# MicroFans.net
KiCad netlist of a schematic drawn in EAGLE
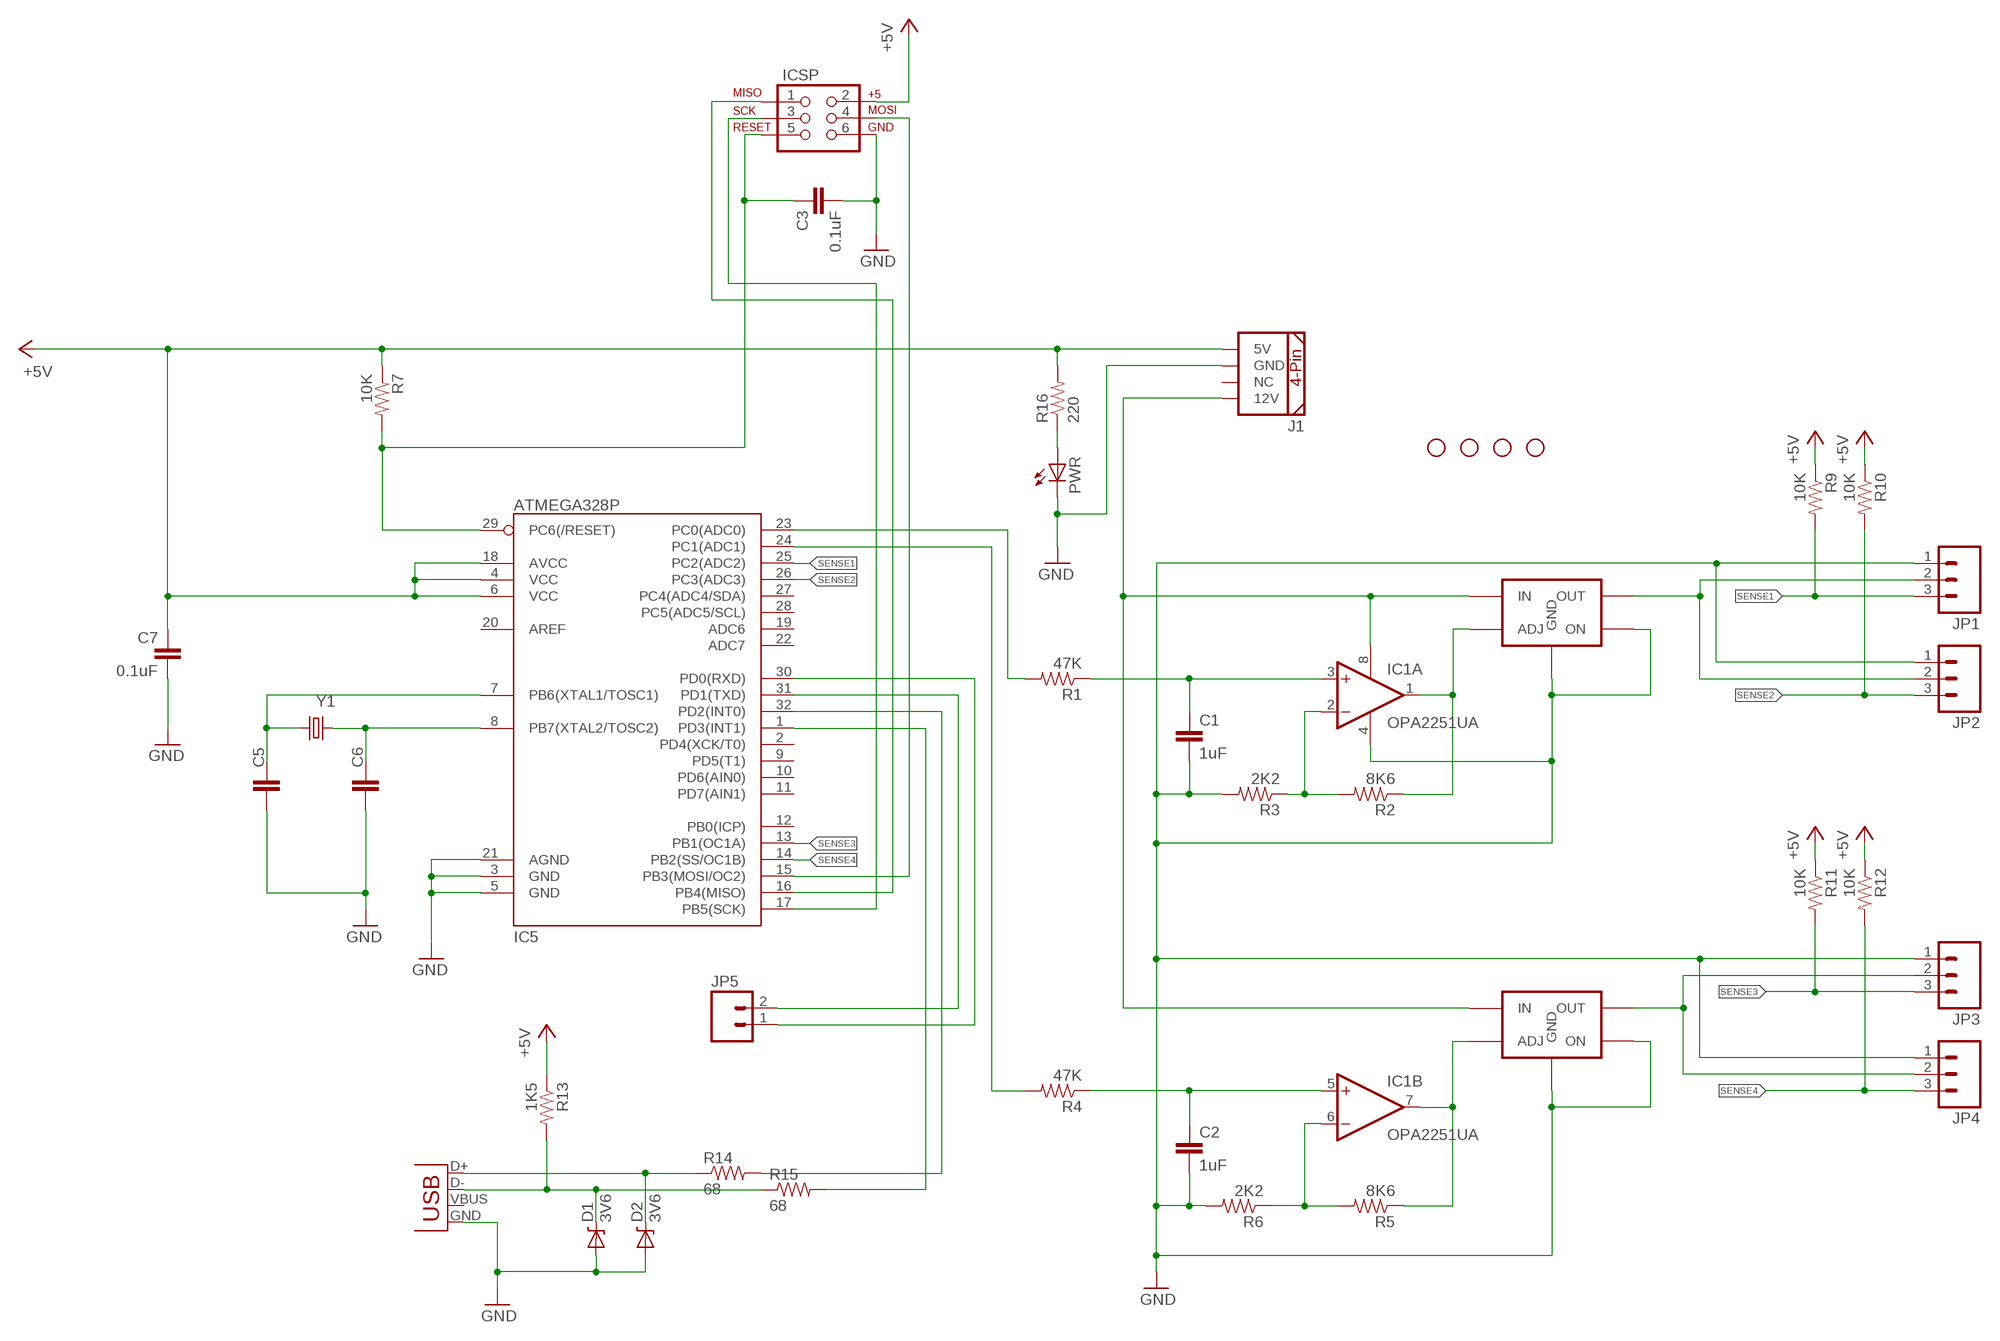
[diagram p0: schematic, sheet 1]

(export (version "E")
  (design (tool "Eeschema 10.0.6"))
  (components
    (comp (ref "C1")
      (value "1uF")
      (footprint "eagle-import:0805")
      (libsource (lib "eagle-import") (part "CAP0805"))
    )
    (comp (ref "C2")
      (value "1uF")
      (footprint "eagle-import:0805")
      (libsource (lib "eagle-import") (part "CAP0805"))
    )
    (comp (ref "C3")
      (value "0.1uF")
      (footprint "eagle-import:0805")
      (libsource (lib "eagle-import") (part "CAP0805"))
    )
    (comp (ref "C5")
      (value ".22uF")
      (footprint "eagle-import:0805")
      (libsource (lib "eagle-import") (part "CAP0805"))
    )
    (comp (ref "C6")
      (value ".22uF")
      (footprint "eagle-import:0805")
      (libsource (lib "eagle-import") (part "CAP0805"))
    )
    (comp (ref "C7")
      (value "0.1uF")
      (footprint "eagle-import:0805")
      (libsource (lib "eagle-import") (part "CAP0805"))
    )
    (comp (ref "D1")
      (value "3V6")
      (footprint "eagle-import:SOD-323")
      (libsource (lib "eagle-import") (part "DIODE-ZENER-BZT52"))
    )
    (comp (ref "D2")
      (value "3V6")
      (footprint "eagle-import:SOD-323")
      (libsource (lib "eagle-import") (part "DIODE-ZENER-BZT52"))
    )
    (comp (ref "HOLE1")
      (value "STAND-OFF")
      (footprint "eagle-import:STAND-OFF")
      (libsource (lib "eagle-import") (part "STAND-OFF"))
    )
    (comp (ref "HOLE2")
      (value "STAND-OFF")
      (footprint "eagle-import:STAND-OFF")
      (libsource (lib "eagle-import") (part "STAND-OFF"))
    )
    (comp (ref "HOLE3")
      (value "STAND-OFF")
      (footprint "eagle-import:STAND-OFF")
      (libsource (lib "eagle-import") (part "STAND-OFF"))
    )
    (comp (ref "HOLE4")
      (value "STAND-OFF")
      (footprint "eagle-import:STAND-OFF")
      (libsource (lib "eagle-import") (part "STAND-OFF"))
    )
    (comp (ref "IC1")
      (value "OPA2251UA")
      (footprint "eagle-import:SO08")
      (libsource (lib "eagle-import") (part "OPA2UA251"))
    )
    (comp (ref "IC3")
      (value "LM2941TO220-V")
      (footprint "eagle-import:TO220-51")
      (libsource (lib "eagle-import") (part "LM2941TO220-V"))
    )
    (comp (ref "IC4")
      (value "LM2941TO220-V")
      (footprint "eagle-import:TO220-51")
      (libsource (lib "eagle-import") (part "LM2941TO220-V"))
    )
    (comp (ref "IC5")
      (value "ATMEGA328P")
      (footprint "eagle-import:TQFP32-08")
      (libsource (lib "eagle-import") (part "ATMEGA328_SMT"))
    )
    (comp (ref "ICSP")
      (value "AVR_SPI_PRG_6PTH")
      (footprint "eagle-import:2X3")
      (libsource (lib "eagle-import") (part "AVR_SPI_PRG_6PTH"))
    )
    (comp (ref "J1")
      (value "COMPUTER-PERIPHERAL-POWERVERTICAL")
      (footprint "eagle-import:COMPUTER-PERIPHERAL-POWER")
      (libsource (lib "eagle-import") (part "COMPUTER-PERIPHERAL-POWERVERTICAL"))
    )
    (comp (ref "JP1")
      (value "M03POLAR")
      (footprint "eagle-import:MOLEX-1X3")
      (libsource (lib "eagle-import") (part "M03POLAR"))
    )
    (comp (ref "JP2")
      (value "M03POLAR")
      (footprint "eagle-import:MOLEX-1X3")
      (libsource (lib "eagle-import") (part "M03POLAR"))
    )
    (comp (ref "JP3")
      (value "M03POLAR")
      (footprint "eagle-import:MOLEX-1X3")
      (libsource (lib "eagle-import") (part "M03POLAR"))
    )
    (comp (ref "JP4")
      (value "M03POLAR")
      (footprint "eagle-import:MOLEX-1X3")
      (libsource (lib "eagle-import") (part "M03POLAR"))
    )
    (comp (ref "JP5")
      (value "M02PTH")
      (footprint "eagle-import:1X02")
      (libsource (lib "eagle-import") (part "M02PTH"))
    )
    (comp (ref "PWR")
      (value "LED1206")
      (footprint "eagle-import:LED-1206")
      (libsource (lib "eagle-import") (part "LED1206"))
    )
    (comp (ref "R1")
      (value "47K")
      (footprint "eagle-import:0805")
      (libsource (lib "eagle-import") (part "RESISTOR0805-RES"))
    )
    (comp (ref "R2")
      (value "8K6")
      (footprint "eagle-import:0805")
      (libsource (lib "eagle-import") (part "RESISTOR0805-RES"))
    )
    (comp (ref "R3")
      (value "2K2")
      (footprint "eagle-import:0805")
      (libsource (lib "eagle-import") (part "RESISTOR0805-RES"))
    )
    (comp (ref "R4")
      (value "47K")
      (footprint "eagle-import:0805")
      (libsource (lib "eagle-import") (part "RESISTOR0805-RES"))
    )
    (comp (ref "R5")
      (value "8K6")
      (footprint "eagle-import:0805")
      (libsource (lib "eagle-import") (part "RESISTOR0805-RES"))
    )
    (comp (ref "R6")
      (value "2K2")
      (footprint "eagle-import:0805")
      (libsource (lib "eagle-import") (part "RESISTOR0805-RES"))
    )
    (comp (ref "R7")
      (value "10K")
      (footprint "eagle-import:0805")
      (libsource (lib "eagle-import") (part "RESISTOR0805-RES"))
    )
    (comp (ref "R9")
      (value "10K")
      (footprint "eagle-import:0805")
      (libsource (lib "eagle-import") (part "RESISTOR0805-RES"))
    )
    (comp (ref "R10")
      (value "10K")
      (footprint "eagle-import:0805")
      (libsource (lib "eagle-import") (part "RESISTOR0805-RES"))
    )
    (comp (ref "R11")
      (value "10K")
      (footprint "eagle-import:0805")
      (libsource (lib "eagle-import") (part "RESISTOR0805-RES"))
    )
    (comp (ref "R12")
      (value "10K")
      (footprint "eagle-import:0805")
      (libsource (lib "eagle-import") (part "RESISTOR0805-RES"))
    )
    (comp (ref "R13")
      (value "1K5")
      (footprint "eagle-import:0805")
      (libsource (lib "eagle-import") (part "RESISTOR0805-RES"))
    )
    (comp (ref "R14")
      (value "68")
      (footprint "eagle-import:0805")
      (libsource (lib "eagle-import") (part "RESISTOR0805-RES"))
    )
    (comp (ref "R15")
      (value "68")
      (footprint "eagle-import:0805")
      (libsource (lib "eagle-import") (part "RESISTOR0805-RES"))
    )
    (comp (ref "R16")
      (value "220")
      (footprint "eagle-import:0805")
      (libsource (lib "eagle-import") (part "RESISTOR0805-RES"))
    )
    (comp (ref "USB")
      (value "USB-A-SMD")
      (footprint "eagle-import:USB-A-S-NOSILK-FEMALE")
      (libsource (lib "eagle-import") (part "USB-A-SMD"))
    )
    (comp (ref "Y1")
      (value "16MHZ")
      (footprint "eagle-import:HC49US")
      (libsource (lib "eagle-import") (part "CRYSTALHC49US"))
    )
  )
  (nets
    (net (code "1") (name "+5V") (class "Default")
      (node (ref "C7") (pin "1") (pinfunction "1_1") (pintype "passive"))
      (node (ref "IC5") (pin "18") (pinfunction "AVCC_18") (pintype "bidirectional"))
      (node (ref "IC5") (pin "4") (pinfunction "VCC_4") (pintype "bidirectional"))
      (node (ref "IC5") (pin "6") (pinfunction "VCC_6") (pintype "bidirectional"))
      (node (ref "ICSP") (pin "2") (pinfunction "2_2") (pintype "passive"))
      (node (ref "J1") (pin "5V") (pinfunction "5V_5V") (pintype "passive"))
      (node (ref "R10") (pin "1") (pinfunction "1_1") (pintype "passive"))
      (node (ref "R11") (pin "1") (pinfunction "1_1") (pintype "passive"))
      (node (ref "R12") (pin "1") (pinfunction "1_1") (pintype "passive"))
      (node (ref "R13") (pin "1") (pinfunction "1_1") (pintype "passive"))
      (node (ref "R16") (pin "2") (pinfunction "2_2") (pintype "passive"))
      (node (ref "R7") (pin "1") (pinfunction "1_1") (pintype "passive"))
      (node (ref "R9") (pin "1") (pinfunction "1_1") (pintype "passive"))
    )
    (net (code "2") (name "GND") (class "Default")
      (node (ref "C1") (pin "2") (pinfunction "2_2") (pintype "passive"))
      (node (ref "C2") (pin "2") (pinfunction "2_2") (pintype "passive"))
      (node (ref "C3") (pin "2") (pinfunction "2_2") (pintype "passive"))
      (node (ref "C5") (pin "2") (pinfunction "2_2") (pintype "passive"))
      (node (ref "C6") (pin "2") (pinfunction "2_2") (pintype "passive"))
      (node (ref "C7") (pin "2") (pinfunction "2_2") (pintype "passive"))
      (node (ref "D1") (pin "2") (pinfunction "A_2") (pintype "passive"))
      (node (ref "D2") (pin "2") (pinfunction "A_2") (pintype "passive"))
      (node (ref "IC1") (pin "4") (pinfunction "V-_4") (pintype "power_in"))
      (node (ref "IC3") (pin "2") (pinfunction "ON_2") (pintype "bidirectional"))
      (node (ref "IC3") (pin "3") (pinfunction "GND_3") (pintype "bidirectional"))
      (node (ref "IC4") (pin "2") (pinfunction "ON_2") (pintype "bidirectional"))
      (node (ref "IC4") (pin "3") (pinfunction "GND_3") (pintype "bidirectional"))
      (node (ref "IC5") (pin "21") (pinfunction "AGND_21") (pintype "bidirectional"))
      (node (ref "IC5") (pin "3") (pinfunction "GND_3") (pintype "bidirectional"))
      (node (ref "IC5") (pin "5") (pinfunction "GND_5") (pintype "bidirectional"))
      (node (ref "ICSP") (pin "6") (pinfunction "6_6") (pintype "passive"))
      (node (ref "J1") (pin "GND") (pinfunction "GND_GND") (pintype "passive"))
      (node (ref "JP1") (pin "1") (pinfunction "1_1") (pintype "passive"))
      (node (ref "JP2") (pin "1") (pinfunction "1_1") (pintype "passive"))
      (node (ref "JP3") (pin "1") (pinfunction "1_1") (pintype "passive"))
      (node (ref "JP4") (pin "1") (pinfunction "1_1") (pintype "passive"))
      (node (ref "PWR") (pin "C") (pinfunction "C_C") (pintype "passive"))
      (node (ref "R3") (pin "2") (pinfunction "2_2") (pintype "passive"))
      (node (ref "R6") (pin "2") (pinfunction "2_2") (pintype "passive"))
      (node (ref "USB") (pin "GND") (pinfunction "GND_GND") (pintype "bidirectional"))
    )
    (net (code "3") (name "Net-(D1-C)") (class "Default")
      (node (ref "D1") (pin "1") (pinfunction "C_1") (pintype "passive"))
      (node (ref "R13") (pin "2") (pinfunction "2_2") (pintype "passive"))
      (node (ref "R15") (pin "1") (pinfunction "1_1") (pintype "passive"))
      (node (ref "USB") (pin "D-") (pinfunction "D-_D-") (pintype "bidirectional"))
    )
    (net (code "4") (name "Net-(D2-C)") (class "Default")
      (node (ref "D2") (pin "1") (pinfunction "C_1") (pintype "passive"))
      (node (ref "R14") (pin "1") (pinfunction "1_1") (pintype "passive"))
      (node (ref "USB") (pin "D+") (pinfunction "D+_D+") (pintype "bidirectional"))
    )
    (net (code "5") (name "Net-(IC1A-+IN)") (class "Default")
      (node (ref "C1") (pin "1") (pinfunction "1_1") (pintype "passive"))
      (node (ref "IC1") (pin "3") (pinfunction "+IN_3") (pintype "input"))
      (node (ref "R1") (pin "1") (pinfunction "1_1") (pintype "passive"))
    )
    (net (code "6") (name "Net-(IC1A--IN)") (class "Default")
      (node (ref "IC1") (pin "2") (pinfunction "-IN_2") (pintype "input"))
      (node (ref "R2") (pin "2") (pinfunction "2_2") (pintype "passive"))
      (node (ref "R3") (pin "1") (pinfunction "1_1") (pintype "passive"))
    )
    (net (code "7") (name "Net-(IC1A-OUT)") (class "Default")
      (node (ref "IC1") (pin "1") (pinfunction "OUT_1") (pintype "output"))
      (node (ref "IC3") (pin "1") (pinfunction "ADJ_1") (pintype "bidirectional"))
      (node (ref "R2") (pin "1") (pinfunction "1_1") (pintype "passive"))
    )
    (net (code "8") (name "Net-(IC1A-V+)") (class "Default")
      (node (ref "IC1") (pin "8") (pinfunction "V+_8") (pintype "power_in"))
      (node (ref "IC3") (pin "4") (pinfunction "IN_4") (pintype "bidirectional"))
      (node (ref "IC4") (pin "4") (pinfunction "IN_4") (pintype "bidirectional"))
      (node (ref "J1") (pin "12V") (pinfunction "12V_12V") (pintype "passive"))
    )
    (net (code "9") (name "Net-(IC1B-+IN)") (class "Default")
      (node (ref "C2") (pin "1") (pinfunction "1_1") (pintype "passive"))
      (node (ref "IC1") (pin "5") (pinfunction "+IN_5") (pintype "input"))
      (node (ref "R4") (pin "1") (pinfunction "1_1") (pintype "passive"))
    )
    (net (code "10") (name "Net-(IC1B--IN)") (class "Default")
      (node (ref "IC1") (pin "6") (pinfunction "-IN_6") (pintype "input"))
      (node (ref "R5") (pin "2") (pinfunction "2_2") (pintype "passive"))
      (node (ref "R6") (pin "1") (pinfunction "1_1") (pintype "passive"))
    )
    (net (code "11") (name "Net-(IC1B-OUT)") (class "Default")
      (node (ref "IC1") (pin "7") (pinfunction "OUT_7") (pintype "output"))
      (node (ref "IC4") (pin "1") (pinfunction "ADJ_1") (pintype "bidirectional"))
      (node (ref "R5") (pin "1") (pinfunction "1_1") (pintype "passive"))
    )
    (net (code "12") (name "Net-(IC3-OUT)") (class "Default")
      (node (ref "IC3") (pin "5") (pinfunction "OUT_5") (pintype "bidirectional"))
      (node (ref "JP1") (pin "2") (pinfunction "2_2") (pintype "passive"))
      (node (ref "JP2") (pin "2") (pinfunction "2_2") (pintype "passive"))
    )
    (net (code "13") (name "Net-(IC4-OUT)") (class "Default")
      (node (ref "IC4") (pin "5") (pinfunction "OUT_5") (pintype "bidirectional"))
      (node (ref "JP3") (pin "2") (pinfunction "2_2") (pintype "passive"))
      (node (ref "JP4") (pin "2") (pinfunction "2_2") (pintype "passive"))
    )
    (net (code "14") (name "Net-(IC5-PB3(MOSI{slash}OC2))") (class "Default")
      (node (ref "IC5") (pin "15") (pinfunction "PB3(MOSI/OC2)_15") (pintype "bidirectional"))
      (node (ref "ICSP") (pin "4") (pinfunction "4_4") (pintype "passive"))
    )
    (net (code "15") (name "Net-(IC5-PB4(MISO))") (class "Default")
      (node (ref "IC5") (pin "16") (pinfunction "PB4(MISO)_16") (pintype "bidirectional"))
      (node (ref "ICSP") (pin "1") (pinfunction "1_1") (pintype "passive"))
    )
    (net (code "16") (name "Net-(IC5-PB5(SCK))") (class "Default")
      (node (ref "IC5") (pin "17") (pinfunction "PB5(SCK)_17") (pintype "bidirectional"))
      (node (ref "ICSP") (pin "3") (pinfunction "3_3") (pintype "passive"))
    )
    (net (code "17") (name "Net-(IC5-PB6(XTAL1{slash}TOSC1))") (class "Default")
      (node (ref "C5") (pin "1") (pinfunction "1_1") (pintype "passive"))
      (node (ref "IC5") (pin "7") (pinfunction "PB6(XTAL1/TOSC1)_7") (pintype "bidirectional"))
      (node (ref "Y1") (pin "2") (pinfunction "2_2") (pintype "passive"))
    )
    (net (code "18") (name "Net-(IC5-PB7(XTAL2{slash}TOSC2))") (class "Default")
      (node (ref "C6") (pin "1") (pinfunction "1_1") (pintype "passive"))
      (node (ref "IC5") (pin "8") (pinfunction "PB7(XTAL2/TOSC2)_8") (pintype "bidirectional"))
      (node (ref "Y1") (pin "1") (pinfunction "1_1") (pintype "passive"))
    )
    (net (code "19") (name "Net-(IC5-PC0(ADC0))") (class "Default")
      (node (ref "IC5") (pin "23") (pinfunction "PC0(ADC0)_23") (pintype "bidirectional"))
      (node (ref "R1") (pin "2") (pinfunction "2_2") (pintype "passive"))
    )
    (net (code "20") (name "Net-(IC5-PC1(ADC1))") (class "Default")
      (node (ref "IC5") (pin "24") (pinfunction "PC1(ADC1)_24") (pintype "bidirectional"))
      (node (ref "R4") (pin "2") (pinfunction "2_2") (pintype "passive"))
    )
    (net (code "21") (name "Net-(IC5-PC6({slash}RESET))") (class "Default")
      (node (ref "C3") (pin "1") (pinfunction "1_1") (pintype "passive"))
      (node (ref "IC5") (pin "29") (pinfunction "PC6(/RESET)_29") (pintype "bidirectional"))
      (node (ref "ICSP") (pin "5") (pinfunction "5_5") (pintype "passive"))
      (node (ref "R7") (pin "2") (pinfunction "2_2") (pintype "passive"))
    )
    (net (code "22") (name "Net-(IC5-PD0(RXD))") (class "Default")
      (node (ref "IC5") (pin "30") (pinfunction "PD0(RXD)_30") (pintype "bidirectional"))
      (node (ref "JP5") (pin "1") (pinfunction "1_1") (pintype "passive"))
    )
    (net (code "23") (name "Net-(IC5-PD1(TXD))") (class "Default")
      (node (ref "IC5") (pin "31") (pinfunction "PD1(TXD)_31") (pintype "bidirectional"))
      (node (ref "JP5") (pin "2") (pinfunction "2_2") (pintype "passive"))
    )
    (net (code "24") (name "Net-(IC5-PD2(INT0))") (class "Default")
      (node (ref "IC5") (pin "32") (pinfunction "PD2(INT0)_32") (pintype "bidirectional"))
      (node (ref "R14") (pin "2") (pinfunction "2_2") (pintype "passive"))
    )
    (net (code "25") (name "Net-(IC5-PD3(INT1))") (class "Default")
      (node (ref "IC5") (pin "1") (pinfunction "PD3(INT1)_1") (pintype "bidirectional"))
      (node (ref "R15") (pin "2") (pinfunction "2_2") (pintype "passive"))
    )
    (net (code "26") (name "Net-(PWR-PadA)") (class "Default")
      (node (ref "PWR") (pin "A") (pinfunction "A_A") (pintype "passive"))
      (node (ref "R16") (pin "1") (pinfunction "1_1") (pintype "passive"))
    )
    (net (code "27") (name "SENSE1") (class "Default")
      (node (ref "IC5") (pin "25") (pinfunction "PC2(ADC2)_25") (pintype "bidirectional"))
      (node (ref "JP1") (pin "3") (pinfunction "3_3") (pintype "passive"))
      (node (ref "R9") (pin "2") (pinfunction "2_2") (pintype "passive"))
    )
    (net (code "28") (name "SENSE2") (class "Default")
      (node (ref "IC5") (pin "26") (pinfunction "PC3(ADC3)_26") (pintype "bidirectional"))
      (node (ref "JP2") (pin "3") (pinfunction "3_3") (pintype "passive"))
      (node (ref "R10") (pin "2") (pinfunction "2_2") (pintype "passive"))
    )
    (net (code "29") (name "SENSE3") (class "Default")
      (node (ref "IC5") (pin "13") (pinfunction "PB1(OC1A)_13") (pintype "bidirectional"))
      (node (ref "JP3") (pin "3") (pinfunction "3_3") (pintype "passive"))
      (node (ref "R11") (pin "2") (pinfunction "2_2") (pintype "passive"))
    )
    (net (code "30") (name "SENSE4") (class "Default")
      (node (ref "IC5") (pin "14") (pinfunction "PB2(SS/OC1B)_14") (pintype "bidirectional"))
      (node (ref "JP4") (pin "3") (pinfunction "3_3") (pintype "passive"))
      (node (ref "R12") (pin "2") (pinfunction "2_2") (pintype "passive"))
    )
    (net (code "31") (name "unconnected-(IC5-ADC6-Pad19)") (class "Default")
      (node (ref "IC5") (pin "19") (pinfunction "ADC6_19") (pintype "bidirectional"))
    )
    (net (code "32") (name "unconnected-(IC5-ADC7-Pad22)") (class "Default")
      (node (ref "IC5") (pin "22") (pinfunction "ADC7_22") (pintype "bidirectional"))
    )
    (net (code "33") (name "unconnected-(IC5-AREF-Pad20)") (class "Default")
      (node (ref "IC5") (pin "20") (pinfunction "AREF_20") (pintype "bidirectional"))
    )
    (net (code "34") (name "unconnected-(IC5-PB0(ICP)-Pad12)") (class "Default")
      (node (ref "IC5") (pin "12") (pinfunction "PB0(ICP)_12") (pintype "bidirectional"))
    )
    (net (code "35") (name "unconnected-(IC5-PC4(ADC4{slash}SDA)-Pad27)") (class "Default")
      (node (ref "IC5") (pin "27") (pinfunction "PC4(ADC4/SDA)_27") (pintype "bidirectional"))
    )
    (net (code "36") (name "unconnected-(IC5-PC5(ADC5{slash}SCL)-Pad28)") (class "Default")
      (node (ref "IC5") (pin "28") (pinfunction "PC5(ADC5/SCL)_28") (pintype "bidirectional"))
    )
    (net (code "37") (name "unconnected-(IC5-PD4(XCK{slash}T0)-Pad2)") (class "Default")
      (node (ref "IC5") (pin "2") (pinfunction "PD4(XCK/T0)_2") (pintype "bidirectional"))
    )
    (net (code "38") (name "unconnected-(IC5-PD5(T1)-Pad9)") (class "Default")
      (node (ref "IC5") (pin "9") (pinfunction "PD5(T1)_9") (pintype "bidirectional"))
    )
    (net (code "39") (name "unconnected-(IC5-PD6(AIN0)-Pad10)") (class "Default")
      (node (ref "IC5") (pin "10") (pinfunction "PD6(AIN0)_10") (pintype "bidirectional"))
    )
    (net (code "40") (name "unconnected-(IC5-PD7(AIN1)-Pad11)") (class "Default")
      (node (ref "IC5") (pin "11") (pinfunction "PD7(AIN1)_11") (pintype "bidirectional"))
    )
    (net (code "41") (name "unconnected-(J1-PadNC)") (class "Default")
      (node (ref "J1") (pin "NC") (pinfunction "NC_NC") (pintype "passive"))
    )
    (net (code "42") (name "unconnected-(USB-PadVBUS)") (class "Default")
      (node (ref "USB") (pin "VBUS") (pinfunction "VBUS_VBUS") (pintype "bidirectional"))
    )
  )
)
